# 21.net
KiCad netlist of a schematic drawn in Altium Designer
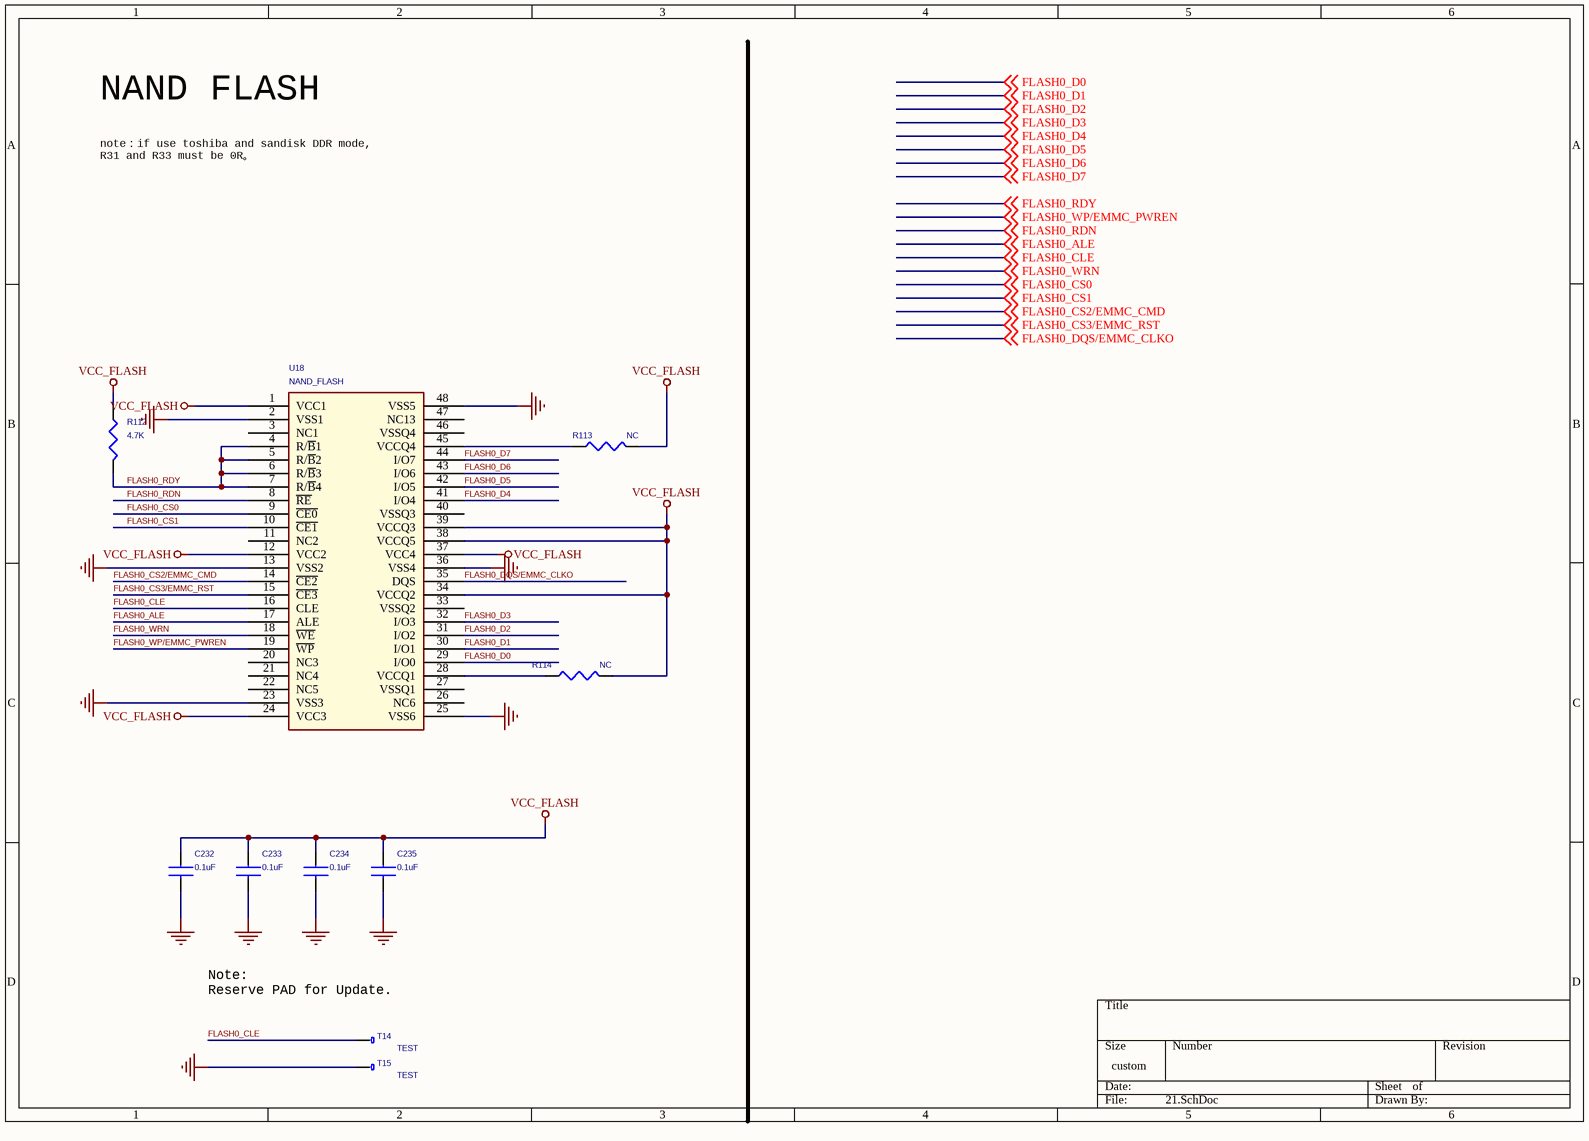
[diagram p0: 21.SchDoc]

(export (version "E")
  (design (tool "Eeschema 10.0.6"))
  (components
    (comp (ref "C232")
      (value "0.1uF")
      (footprint "C0603")
      (description "RoHS CHIP CAP 0.1uF +10/-10% X7R")
      (libsource (lib "*") (part "CAP NP_Dup3"))
    )
    (comp (ref "C233")
      (value "0.1uF")
      (footprint "C0603")
      (description "RoHS CHIP CAP 0.1uF +10/-10% X7R")
      (libsource (lib "*") (part "CAP NP_Dup3"))
    )
    (comp (ref "C234")
      (value "0.1uF")
      (footprint "C0603")
      (description "RoHS CHIP CAP 0.1uF +10/-10% X7R")
      (libsource (lib "*") (part "CAP NP_Dup3"))
    )
    (comp (ref "C235")
      (value "0.1uF")
      (footprint "C0603")
      (description "RoHS CHIP CAP 0.1uF +10/-10% X7R")
      (libsource (lib "*") (part "CAP NP_Dup3"))
    )
    (comp (ref "R112")
      (value "4.7K")
      (footprint "R0402")
      (description "ROHS CHIP RES 4.7K 1/16W +/-5%")
      (libsource (lib "*") (part "RESISTOR_Dup1"))
    )
    (comp (ref "R113") (value "NC") (footprint "R0402") (libsource (lib "*") (part "RESISTOR_Dup1")))
    (comp (ref "R114") (value "NC") (footprint "R0402") (libsource (lib "*") (part "RESISTOR_Dup1")))
    (comp (ref "T14")
      (value "TEST")
      (footprint "TEST")
      (description "test")
      (libsource (lib "*") (part "TEST_1"))
    )
    (comp (ref "T15")
      (value "TEST")
      (footprint "TEST")
      (description "test")
      (libsource (lib "*") (part "TEST_1"))
    )
    (comp (ref "U18")
      (value "NAND_FLASH")
      (footprint "TSOP1-48")
      (description "NAND Flash,2.7V,3.3V,3.6V,2G*8,N/A,-40℃~85℃,TSOP-48P")
      (libsource (lib "*") (part "NANDFLASH_0"))
    )
  )
  (nets
    (net (code "1") (name "FLASH0_ALE") (class "Default")
      (node (ref "U18") (pin "17") (pinfunction "ALE_17") (pintype "passive"))
    )
    (net (code "2") (name "FLASH0_CLE") (class "Default")
      (node (ref "T14") (pin "1") (pinfunction "1_1") (pintype "passive"))
      (node (ref "U18") (pin "16") (pinfunction "CLE_16") (pintype "passive"))
    )
    (net (code "3") (name "FLASH0_CS0") (class "Default")
      (node (ref "U18") (pin "9") (pinfunction "~{CE0}_9") (pintype "passive"))
    )
    (net (code "4") (name "FLASH0_CS1") (class "Default")
      (node (ref "U18") (pin "10") (pinfunction "~{CE1}_10") (pintype "passive"))
    )
    (net (code "5") (name "FLASH0_CS2{slash}EMMC_CMD") (class "Default")
      (node (ref "U18") (pin "14") (pinfunction "~{CE2}_14") (pintype "passive"))
    )
    (net (code "6") (name "FLASH0_CS3{slash}EMMC_RST") (class "Default")
      (node (ref "U18") (pin "15") (pinfunction "~{CE3}_15") (pintype "passive"))
    )
    (net (code "7") (name "FLASH0_D0") (class "Default")
      (node (ref "U18") (pin "29") (pinfunction "I/O0_29") (pintype "passive"))
    )
    (net (code "8") (name "FLASH0_D1") (class "Default")
      (node (ref "U18") (pin "30") (pinfunction "I/O1_30") (pintype "passive"))
    )
    (net (code "9") (name "FLASH0_D2") (class "Default")
      (node (ref "U18") (pin "31") (pinfunction "I/O2_31") (pintype "passive"))
    )
    (net (code "10") (name "FLASH0_D3") (class "Default")
      (node (ref "U18") (pin "32") (pinfunction "I/O3_32") (pintype "passive"))
    )
    (net (code "11") (name "FLASH0_D4") (class "Default")
      (node (ref "U18") (pin "41") (pinfunction "I/O4_41") (pintype "passive"))
    )
    (net (code "12") (name "FLASH0_D5") (class "Default")
      (node (ref "U18") (pin "42") (pinfunction "I/O5_42") (pintype "passive"))
    )
    (net (code "13") (name "FLASH0_D6") (class "Default")
      (node (ref "U18") (pin "43") (pinfunction "I/O6_43") (pintype "passive"))
    )
    (net (code "14") (name "FLASH0_D7") (class "Default")
      (node (ref "U18") (pin "44") (pinfunction "I/O7_44") (pintype "passive"))
    )
    (net (code "15") (name "FLASH0_DQS{slash}EMMC_CLKO") (class "Default")
      (node (ref "U18") (pin "35") (pinfunction "DQS_35") (pintype "passive"))
    )
    (net (code "16") (name "FLASH0_RDN") (class "Default")
      (node (ref "U18") (pin "8") (pinfunction "~{RE}_8") (pintype "passive"))
    )
    (net (code "17") (name "FLASH0_RDY") (class "Default")
      (node (ref "R112") (pin "2") (pinfunction "2_2") (pintype "passive"))
      (node (ref "U18") (pin "4") (pinfunction "R/~{B}1_4") (pintype "passive"))
      (node (ref "U18") (pin "5") (pinfunction "R/~{B}2_5") (pintype "passive"))
      (node (ref "U18") (pin "6") (pinfunction "R/~{B}3_6") (pintype "passive"))
      (node (ref "U18") (pin "7") (pinfunction "R/~{B}4_7") (pintype "passive"))
    )
    (net (code "18") (name "FLASH0_WP{slash}EMMC_PWREN") (class "Default")
      (node (ref "U18") (pin "19") (pinfunction "~{WP}_19") (pintype "passive"))
    )
    (net (code "19") (name "FLASH0_WRN") (class "Default")
      (node (ref "U18") (pin "18") (pinfunction "~{WE}_18") (pintype "passive"))
    )
    (net (code "20") (name "GND") (class "Default")
      (node (ref "C232") (pin "1") (pinfunction "1_1") (pintype "passive"))
      (node (ref "C233") (pin "1") (pinfunction "1_1") (pintype "passive"))
      (node (ref "C234") (pin "1") (pinfunction "1_1") (pintype "passive"))
      (node (ref "C235") (pin "1") (pinfunction "1_1") (pintype "passive"))
      (node (ref "T15") (pin "1") (pinfunction "1_1") (pintype "passive"))
      (node (ref "U18") (pin "13") (pinfunction "VSS2_13") (pintype "power_in"))
      (node (ref "U18") (pin "2") (pinfunction "VSS1_2") (pintype "power_in"))
      (node (ref "U18") (pin "23") (pinfunction "VSS3_23") (pintype "power_in"))
      (node (ref "U18") (pin "25") (pinfunction "VSS6_25") (pintype "power_in"))
      (node (ref "U18") (pin "36") (pinfunction "VSS4_36") (pintype "power_in"))
      (node (ref "U18") (pin "48") (pinfunction "VSS5_48") (pintype "power_in"))
    )
    (net (code "21") (name "Net-(U18-VCCQ1)") (class "Default")
      (node (ref "R114") (pin "1") (pinfunction "1_1") (pintype "passive"))
      (node (ref "U18") (pin "28") (pinfunction "VCCQ1_28") (pintype "passive"))
    )
    (net (code "22") (name "Net-(U18-VCCQ4)") (class "Default")
      (node (ref "R113") (pin "1") (pinfunction "1_1") (pintype "passive"))
      (node (ref "U18") (pin "45") (pinfunction "VCCQ4_45") (pintype "passive"))
    )
    (net (code "23") (name "VCC_FLASH") (class "Default")
      (node (ref "C232") (pin "2") (pinfunction "2_2") (pintype "passive"))
      (node (ref "C233") (pin "2") (pinfunction "2_2") (pintype "passive"))
      (node (ref "C234") (pin "2") (pinfunction "2_2") (pintype "passive"))
      (node (ref "C235") (pin "2") (pinfunction "2_2") (pintype "passive"))
      (node (ref "R112") (pin "1") (pinfunction "1_1") (pintype "passive"))
      (node (ref "R113") (pin "2") (pinfunction "2_2") (pintype "passive"))
      (node (ref "R114") (pin "2") (pinfunction "2_2") (pintype "passive"))
      (node (ref "U18") (pin "1") (pinfunction "VCC1_1") (pintype "power_in"))
      (node (ref "U18") (pin "12") (pinfunction "VCC2_12") (pintype "power_in"))
      (node (ref "U18") (pin "24") (pinfunction "VCC3_24") (pintype "power_in"))
      (node (ref "U18") (pin "34") (pinfunction "VCCQ2_34") (pintype "power_in"))
      (node (ref "U18") (pin "37") (pinfunction "VCC4_37") (pintype "power_in"))
      (node (ref "U18") (pin "38") (pinfunction "VCCQ5_38") (pintype "power_in"))
      (node (ref "U18") (pin "39") (pinfunction "VCCQ3_39") (pintype "power_in"))
    )
    (net (code "24") (name "unconnected-(U18-NC1-Pad3)") (class "Default")
      (node (ref "U18") (pin "3") (pinfunction "NC1_3") (pintype "passive"))
    )
    (net (code "25") (name "unconnected-(U18-NC2-Pad11)") (class "Default")
      (node (ref "U18") (pin "11") (pinfunction "NC2_11") (pintype "passive"))
    )
    (net (code "26") (name "unconnected-(U18-NC3-Pad20)") (class "Default")
      (node (ref "U18") (pin "20") (pinfunction "NC3_20") (pintype "passive"))
    )
    (net (code "27") (name "unconnected-(U18-NC4-Pad21)") (class "Default")
      (node (ref "U18") (pin "21") (pinfunction "NC4_21") (pintype "passive"))
    )
    (net (code "28") (name "unconnected-(U18-NC5-Pad22)") (class "Default")
      (node (ref "U18") (pin "22") (pinfunction "NC5_22") (pintype "passive"))
    )
    (net (code "29") (name "unconnected-(U18-NC6-Pad26)") (class "Default")
      (node (ref "U18") (pin "26") (pinfunction "NC6_26") (pintype "passive"))
    )
    (net (code "30") (name "unconnected-(U18-NC13-Pad47)") (class "Default")
      (node (ref "U18") (pin "47") (pinfunction "NC13_47") (pintype "passive"))
    )
    (net (code "31") (name "unconnected-(U18-VSSQ1-Pad27)") (class "Default")
      (node (ref "U18") (pin "27") (pinfunction "VSSQ1_27") (pintype "passive"))
    )
    (net (code "32") (name "unconnected-(U18-VSSQ2-Pad33)") (class "Default")
      (node (ref "U18") (pin "33") (pinfunction "VSSQ2_33") (pintype "passive"))
    )
    (net (code "33") (name "unconnected-(U18-VSSQ3-Pad40)") (class "Default")
      (node (ref "U18") (pin "40") (pinfunction "VSSQ3_40") (pintype "passive"))
    )
    (net (code "34") (name "unconnected-(U18-VSSQ4-Pad46)") (class "Default")
      (node (ref "U18") (pin "46") (pinfunction "VSSQ4_46") (pintype "passive"))
    )
  )
)
